# 3_Power.net
KiCad netlist of a schematic drawn in Altium Designer
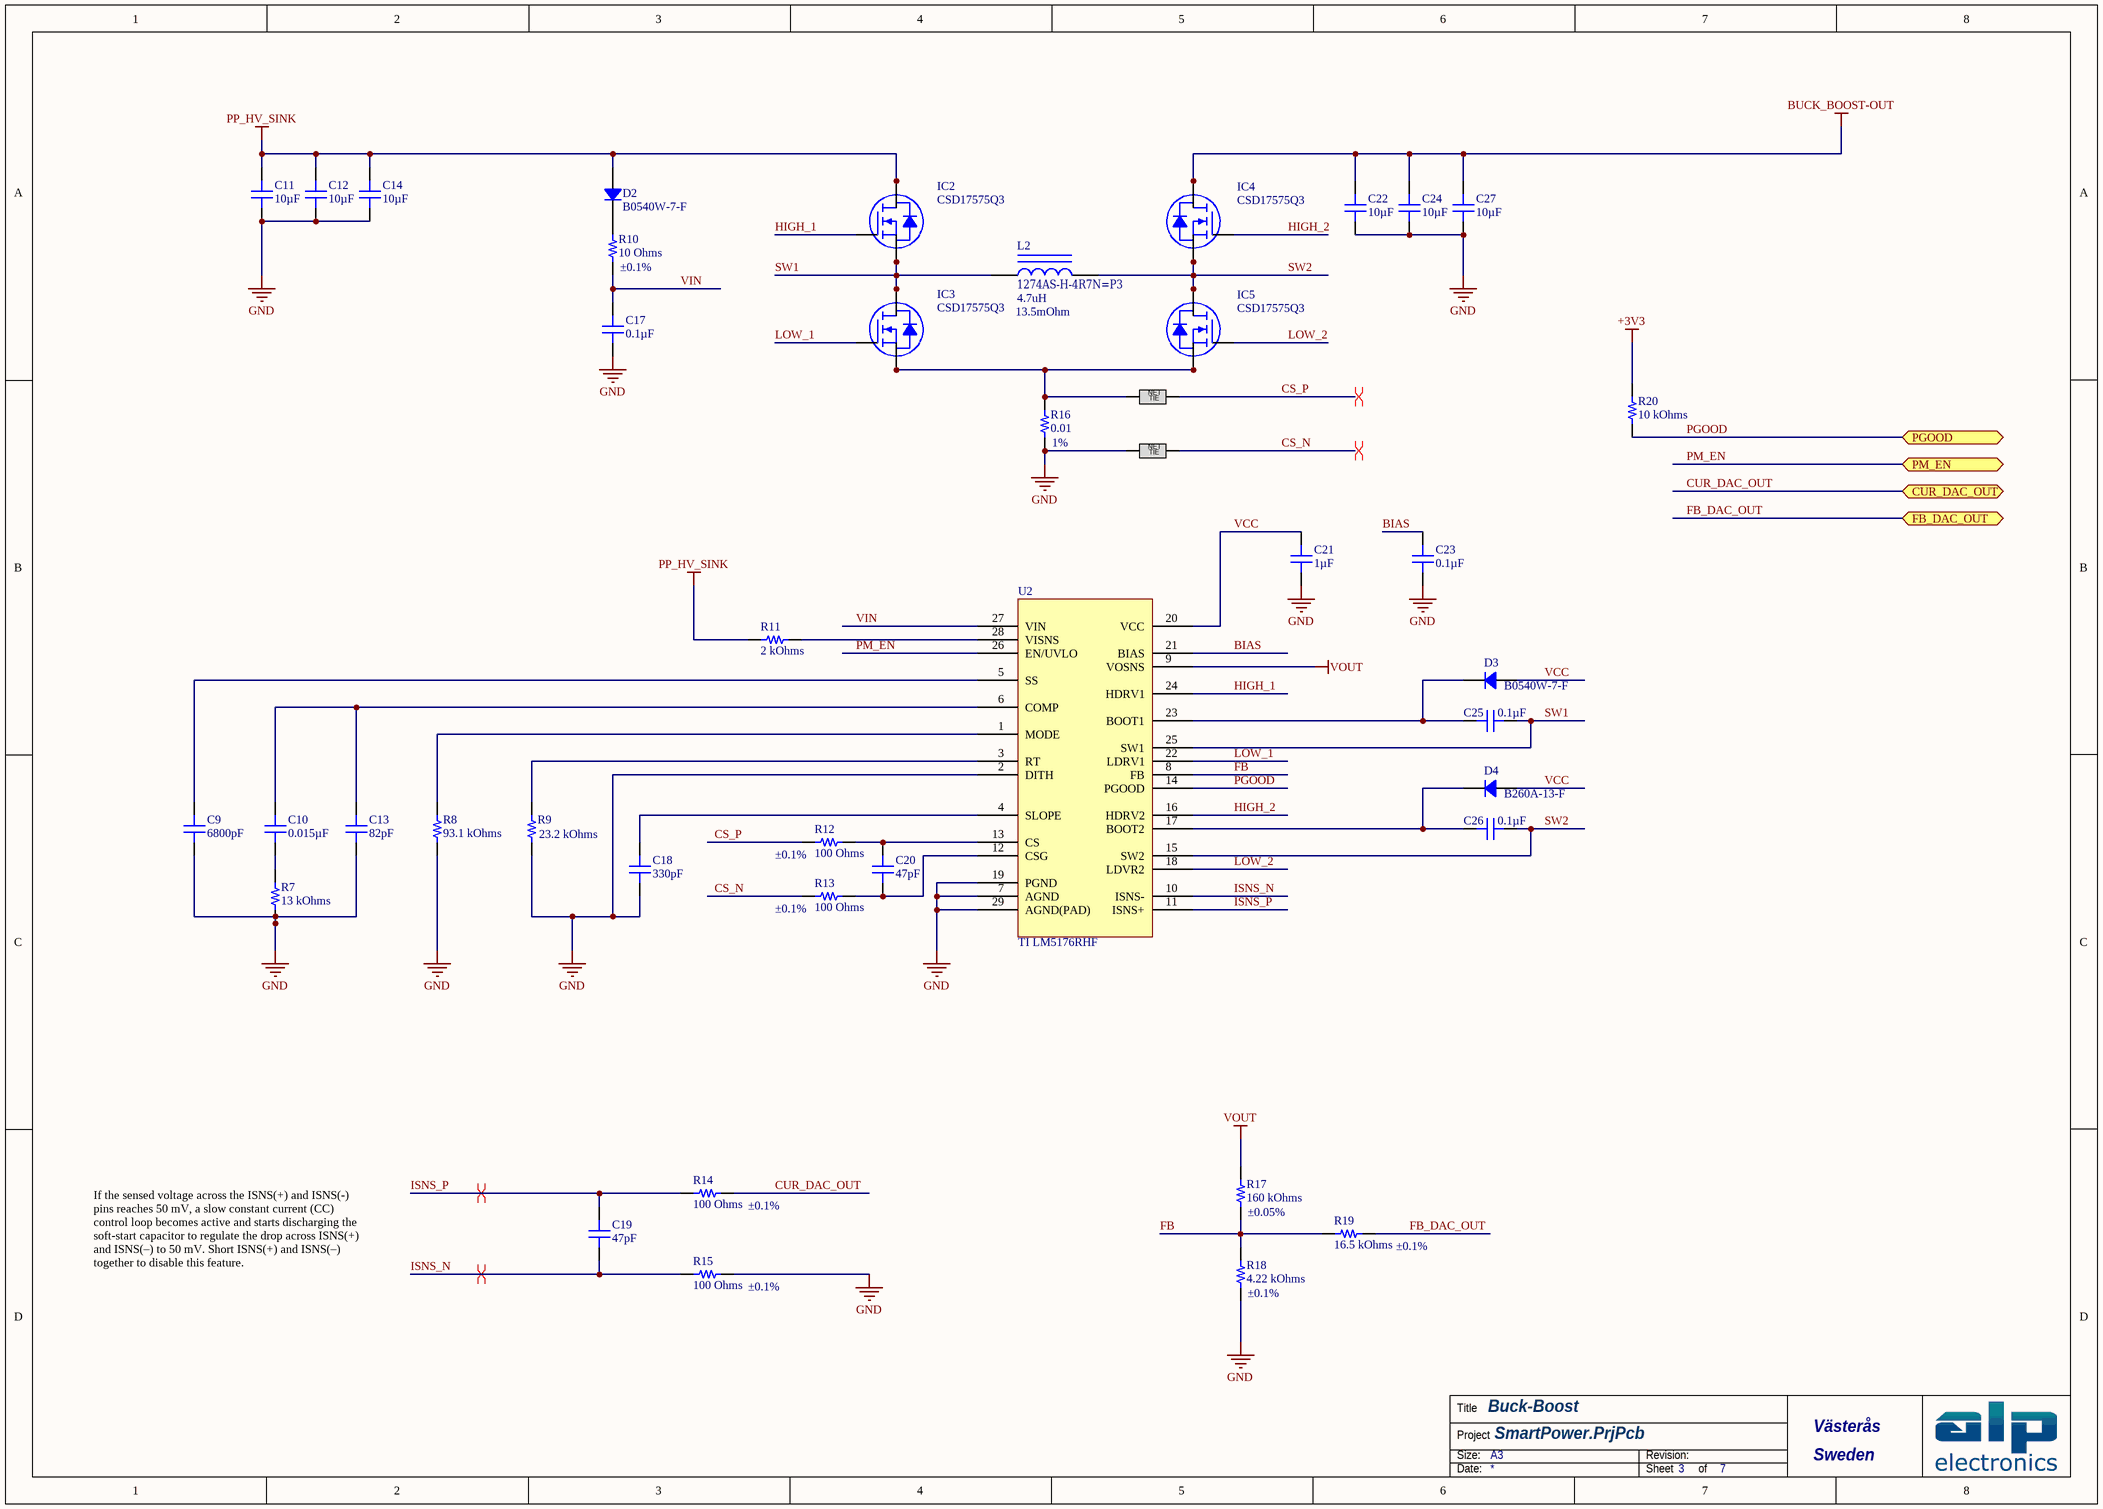
[diagram p0: [3] Power.SchDoc]

(export (version "E")
  (design (tool "Eeschema 10.0.6"))
  (components
    (comp (ref "C9")
      (value "6800pF")
      (footprint "CAP 0603_1608")
      (description "CAP CER 6800PF 50V X7R 0603")
      (fields
        (field (name "PART NUMBER") "0603B682K500CT")
        (field (name "MANUFACTURER") "Walsin Technology Corporation")
      )
      (libsource (lib "Celestial Altium Library - altium_library") (part "Capacitor"))
    )
    (comp (ref "C10")
      (value "0.015µF")
      (footprint "CAP 0603_1608")
      (description "CAP CER 0.015UF 50V X7R 0603")
      (fields
        (field (name "PART NUMBER") "0603B153K500CT")
        (field (name "MANUFACTURER") "Walsin Technology Corporation")
      )
      (libsource (lib "Celestial Altium Library - altium_library") (part "Capacitor"))
    )
    (comp (ref "C11")
      (value "10µF")
      (footprint "CAP 2220_5650 2.5MM")
      (description "CAP CER 10UF 50V X7R 2220")
      (fields
        (field (name "PART NUMBER") "C5750X7R1H106M230KB")
        (field (name "MANUFACTURER") "TDK Corporation")
      )
      (libsource (lib "Celestial Altium Library - altium_library") (part "Capacitor"))
    )
    (comp (ref "C12")
      (value "10µF")
      (footprint "CAP 2220_5650 2.5MM")
      (description "CAP CER 10UF 50V X7R 2220")
      (fields
        (field (name "PART NUMBER") "C5750X7R1H106M230KB")
        (field (name "MANUFACTURER") "TDK Corporation")
      )
      (libsource (lib "Celestial Altium Library - altium_library") (part "Capacitor"))
    )
    (comp (ref "C13")
      (value "82pF")
      (footprint "CAP 0603_1608")
      (description "CAP CER 82PF 100V C0G/NP0 0603")
      (fields (field (name "PART NUMBER") "06031A820GAT2A") (field (name "MANUFACTURER") "AVX Corporation"))
      (libsource (lib "Celestial Altium Library - altium_library") (part "Capacitor"))
    )
    (comp (ref "C14")
      (value "10µF")
      (footprint "CAP 2220_5650 2.5MM")
      (description "CAP CER 10UF 50V X7R 2220")
      (fields
        (field (name "PART NUMBER") "C5750X7R1H106M230KB")
        (field (name "MANUFACTURER") "TDK Corporation")
      )
      (libsource (lib "Celestial Altium Library - altium_library") (part "Capacitor"))
    )
    (comp (ref "C17")
      (value "0.1µF")
      (footprint "CAP 0603_1608")
      (description "CAP CER 0.1UF 50V X7R 0603")
      (fields (field (name "PART NUMBER") "0603BB104K500NGT") (field (name "MANUFACTURER") "Knowles Novacap"))
      (libsource (lib "Celestial Altium Library - altium_library") (part "Capacitor"))
    )
    (comp (ref "C18")
      (value "330pF")
      (footprint "CAP 0603_1608")
      (description "CAP CER 330PF 100V C0G/NP0 0603")
      (fields
        (field (name "PART NUMBER") "0603N331J101CT")
        (field (name "MANUFACTURER") "Walsin Technology Corporation")
      )
      (libsource (lib "Celestial Altium Library - altium_library") (part "Capacitor"))
    )
    (comp (ref "C19")
      (value "47pF")
      (footprint "CAP 0603_1608")
      (description "CAP CER 47PF 50V C0G/NP0 0603")
      (fields
        (field (name "PART NUMBER") "500X14N470MV4T")
        (field (name "MANUFACTURER") "Johanson Dielectrics Inc.")
      )
      (libsource (lib "Celestial Altium Library - altium_library") (part "Capacitor"))
    )
    (comp (ref "C20")
      (value "47pF")
      (footprint "CAP 0603_1608")
      (description "CAP CER 47PF 50V C0G/NP0 0603")
      (fields
        (field (name "PART NUMBER") "500X14N470MV4T")
        (field (name "MANUFACTURER") "Johanson Dielectrics Inc.")
      )
      (libsource (lib "Celestial Altium Library - altium_library") (part "Capacitor"))
    )
    (comp (ref "C21")
      (value "1µF")
      (footprint "CAP 0603_1608")
      (description "CAP CER 1UF 50V X7R 0603")
      (fields (field (name "PART NUMBER") "06035C105KAT2A") (field (name "MANUFACTURER") "AVX Corporation"))
      (libsource (lib "Celestial Altium Library - altium_library") (part "Capacitor"))
    )
    (comp (ref "C22")
      (value "10µF")
      (footprint "CAP 2220_5650 2.5MM")
      (description "CAP CER 10UF 50V X7R 2220")
      (fields
        (field (name "PART NUMBER") "C5750X7R1H106M230KB")
        (field (name "MANUFACTURER") "TDK Corporation")
      )
      (libsource (lib "Celestial Altium Library - altium_library") (part "Capacitor"))
    )
    (comp (ref "C23")
      (value "0.1µF")
      (footprint "CAP 0603_1608")
      (description "CAP CER 0.1UF 50V X7R 0603")
      (fields (field (name "PART NUMBER") "0603BB104K500NGT") (field (name "MANUFACTURER") "Knowles Novacap"))
      (libsource (lib "Celestial Altium Library - altium_library") (part "Capacitor"))
    )
    (comp (ref "C24")
      (value "10µF")
      (footprint "CAP 2220_5650 2.5MM")
      (description "CAP CER 10UF 50V X7R 2220")
      (fields
        (field (name "PART NUMBER") "C5750X7R1H106M230KB")
        (field (name "MANUFACTURER") "TDK Corporation")
      )
      (libsource (lib "Celestial Altium Library - altium_library") (part "Capacitor"))
    )
    (comp (ref "C25")
      (value "0.1µF")
      (footprint "CAP 0603_1608")
      (description "CAP CER 0.1UF 50V X7R 0603")
      (fields (field (name "PART NUMBER") "0603BB104K500NGT") (field (name "MANUFACTURER") "Knowles Novacap"))
      (libsource (lib "Celestial Altium Library - altium_library") (part "Capacitor"))
    )
    (comp (ref "C26")
      (value "0.1µF")
      (footprint "CAP 0603_1608")
      (description "CAP CER 0.1UF 50V X7R 0603")
      (fields (field (name "PART NUMBER") "0603BB104K500NGT") (field (name "MANUFACTURER") "Knowles Novacap"))
      (libsource (lib "Celestial Altium Library - altium_library") (part "Capacitor"))
    )
    (comp (ref "C27")
      (value "10µF")
      (footprint "CAP 2220_5650 2.5MM")
      (description "CAP CER 10UF 50V X7R 2220")
      (fields
        (field (name "PART NUMBER") "C5750X7R1H106M230KB")
        (field (name "MANUFACTURER") "TDK Corporation")
      )
      (libsource (lib "Celestial Altium Library - altium_library") (part "Capacitor"))
    )
    (comp (ref "D2")
      (value "B0540W-7-F")
      (footprint "SOD-123")
      (description "DIODE SCHOTTKY 40V 500MA SOD123")
      (fields (field (name "MANUFACTURER") "Diodes Incorporated"))
      (libsource (lib "Celestial Library Database") (part "Diode"))
    )
    (comp (ref "D3")
      (value "B0540W-7-F")
      (footprint "SOD-123")
      (description "DIODE SCHOTTKY 40V 500MA SOD123")
      (fields (field (name "MANUFACTURER") "Diodes Incorporated"))
      (libsource (lib "Celestial Library Database") (part "Diode"))
    )
    (comp (ref "D4")
      (value "B260A-13-F")
      (footprint "DO214AC SMA")
      (description "DIODE SCHOTTKY 60V 2A SMA")
      (fields (field (name "MANUFACTURER") "Diodes Incorporated"))
      (libsource (lib "Celestial Library Database") (part "Diode"))
    )
    (comp (ref "IC2")
      (value "CSD17575Q3")
      (footprint "TI SON-8 Q3")
      (description "MOSFET N-CH 30V 50A")
      (fields (field (name "PART NUMBER") "CSD17308Q3T") (field (name "MANUFACTURER") "Texas Instruments"))
      (libsource (lib "") (part "TI CSD MOSFET N-CH Q3_1"))
    )
    (comp (ref "IC3")
      (value "CSD17575Q3")
      (footprint "TI SON-8 Q3")
      (description "MOSFET N-CH 30V 50A")
      (fields (field (name "PART NUMBER") "CSD17308Q3T") (field (name "MANUFACTURER") "Texas Instruments"))
      (libsource (lib "") (part "TI CSD MOSFET N-CH Q3_1"))
    )
    (comp (ref "IC4")
      (value "CSD17575Q3")
      (footprint "TI SON-8 Q3")
      (description "MOSFET N-CH 30V 50A")
      (fields (field (name "PART NUMBER") "CSD17308Q3T") (field (name "MANUFACTURER") "Texas Instruments"))
      (libsource (lib "Celestial Library Database") (part "TI CSD MOSFET N-CH Q3"))
    )
    (comp (ref "IC5")
      (value "CSD17575Q3")
      (footprint "TI SON-8 Q3")
      (description "MOSFET N-CH 30V 50A")
      (fields (field (name "PART NUMBER") "CSD17308Q3T") (field (name "MANUFACTURER") "Texas Instruments"))
      (libsource (lib "Celestial Library Database") (part "TI CSD MOSFET N-CH Q3"))
    )
    (comp (ref "L2")
      (value "‎1274AS-H-4R7N=P3‎")
      (footprint "Component 3D Footprint:MURATA 1274AS")
      (description "Magnetic-Core Inductor")
      (fields
        (field (name "ALTIUM_VALUE") "4.7uH")
        (field (name "DCR") "13.5mOhm")
        (field (name "PUBLISHER") "Altium Limited")
      )
      (libsource (lib "Miscellaneous Devices") (part "Inductor Iron"))
    )
    (comp (ref "NetTie1")
      (value "Net Tie")
      (footprint "3D FootPrint_Backup:Net_Tie_2x0.156mm")
      (libsource (lib "Altium Component") (part "Net Tie"))
    )
    (comp (ref "NetTie2")
      (value "Net Tie")
      (footprint "3D FootPrint_Backup:Net_Tie_2x0.156mm")
      (libsource (lib "Altium Component") (part "Net Tie"))
    )
    (comp (ref "R7")
      (value "13 kOhms")
      (footprint "RES 0603_1608")
      (description "RES SMD 13K OHM 0.5% 1/5W 0603")
      (fields
        (field (name "PART NUMBER") "ERJ-PB3D1302V")
        (field (name "MANUFACTURER") "Panasonic Electronic Components")
      )
      (libsource (lib "Celestial Altium Library - altium_library") (part "Resistor"))
    )
    (comp (ref "R8")
      (value "93.1 kOhms")
      (footprint "RES 0603_1608")
      (description "RES SMD 93.1K OHM 0.5% 1/5W 0603")
      (fields
        (field (name "PART NUMBER") "ERJ-PB3D9312V")
        (field (name "MANUFACTURER") "Panasonic Electronic Components")
      )
      (libsource (lib "Celestial Altium Library - altium_library") (part "Resistor"))
    )
    (comp (ref "R9")
      (value "23.2 kOhms")
      (footprint "RES 0603_1608")
      (description "RES 23.2K OHM 0.5% 1/10W 0603")
      (fields
        (field (name "PART NUMBER") "RNCF0603DTE23K2")
        (field (name "MANUFACTURER") "Stackpole Electronics Inc")
      )
      (libsource (lib "Celestial Altium Library - altium_library") (part "Resistor"))
    )
    (comp (ref "R10")
      (value "10 Ohms")
      (footprint "RES 0603_1608")
      (description "RES SMD 10 OHM 0.1% 1/10W 0603")
      (fields
        (field (name "PART NUMBER") "RT0603BRD0710RL")
        (field (name "MANUFACTURER") "Yageo")
        (field (name "TOLERANCE") "±0.1%")
      )
      (libsource (lib "Celestial Altium Library - altium_library") (part "Resistor"))
    )
    (comp (ref "R11")
      (value "2 kOhms")
      (footprint "RES 0603_1608")
      (description "RES SMD 2K OHM 5% 1/10W 0603")
      (fields (field (name "PART NUMBER") "CR0603-JW-202ELF") (field (name "MANUFACTURER") "Bourns Inc."))
      (libsource (lib "Celestial Altium Library - altium_library") (part "Resistor"))
    )
    (comp (ref "R12")
      (value "100 Ohms")
      (footprint "RES 0603_1608")
      (description "RES 100 OHM 0.1% 1/16W 0603")
      (fields
        (field (name "PART NUMBER") "RNCS0603BKE100R")
        (field (name "MANUFACTURER") "Stackpole Electronics Inc")
        (field (name "TOLERANCE") "±0.1%")
      )
      (libsource (lib "Celestial Altium Library - altium_library") (part "Resistor"))
    )
    (comp (ref "R13")
      (value "100 Ohms")
      (footprint "RES 0603_1608")
      (description "RES 100 OHM 0.1% 1/16W 0603")
      (fields
        (field (name "PART NUMBER") "RNCS0603BKE100R")
        (field (name "MANUFACTURER") "Stackpole Electronics Inc")
        (field (name "TOLERANCE") "±0.1%")
      )
      (libsource (lib "Celestial Altium Library - altium_library") (part "Resistor"))
    )
    (comp (ref "R14")
      (value "100 Ohms")
      (footprint "RES 0603_1608")
      (description "RES 100 OHM 0.1% 1/16W 0603")
      (fields
        (field (name "PART NUMBER") "RNCS0603BKE100R")
        (field (name "MANUFACTURER") "Stackpole Electronics Inc")
        (field (name "TOLERANCE") "±0.1%")
      )
      (libsource (lib "Celestial Altium Library - altium_library") (part "Resistor"))
    )
    (comp (ref "R15")
      (value "100 Ohms")
      (footprint "RES 0603_1608")
      (description "RES 100 OHM 0.1% 1/16W 0603")
      (fields
        (field (name "PART NUMBER") "RNCS0603BKE100R")
        (field (name "MANUFACTURER") "Stackpole Electronics Inc")
        (field (name "TOLERANCE") "±0.1%")
      )
      (libsource (lib "Celestial Altium Library - altium_library") (part "Resistor"))
    )
    (comp (ref "R16")
      (value "0.01")
      (footprint "STACKPOLE CSR2512")
      (description "RES SMD 0.01 OHM 1% 2W 2512")
      (fields
        (field (name "PART NUMBER") "CSR2512FK10L0")
        (field (name "MANUFACTURER") "Stackpole Electronics Inc.")
        (field (name "TOLERANCE") "1%")
      )
      (libsource (lib "Celestial Library Database") (part "Resistor"))
    )
    (comp (ref "R17")
      (value "160 kOhms")
      (footprint "RES 0603_1608")
      (description "RES SMD 160KOHM 0.05% 1/10W 0603")
      (fields
        (field (name "PART NUMBER") "RG1608N-164-W-T1")
        (field (name "MANUFACTURER") "Susumu")
        (field (name "TOLERANCE") "±0.05%")
      )
      (libsource (lib "Celestial Altium Library - altium_library") (part "Resistor"))
    )
    (comp (ref "R18")
      (value "4.22 kOhms")
      (footprint "RES 0603_1608")
      (description "RES SMD 4.22K OHM 0.1% 1/5W 0603")
      (fields
        (field (name "PART NUMBER") "ERJ-PB3B4221V")
        (field (name "MANUFACTURER") "Panasonic Electronic Components")
        (field (name "TOLERANCE") "±0.1%")
      )
      (libsource (lib "Celestial Altium Library - altium_library") (part "Resistor"))
    )
    (comp (ref "R19")
      (value "16.5 kOhms")
      (footprint "RES 0603_1608")
      (description "RES SMD 16.5KOHM 0.1% 1/10W 0603")
      (fields
        (field (name "PART NUMBER") "ERA-3AEB1652V")
        (field (name "MANUFACTURER") "Panasonic Electronic Components")
        (field (name "TOLERANCE") "±0.1%")
      )
      (libsource (lib "Celestial Altium Library - altium_library") (part "Resistor"))
    )
    (comp (ref "R20")
      (value "10 kOhms")
      (footprint "RES 0603_1608")
      (description "RES SMD 10K OHM 5% 1/10W 0603")
      (fields (field (name "PART NUMBER") "CRCW060310K0JNEA") (field (name "MANUFACTURER") "Vishay Dale"))
      (libsource (lib "Celestial Altium Library - altium_library") (part "Resistor"))
    )
    (comp (ref "U2")
      (value "TI LM5176RHF")
      (footprint "Leadless:TI VQFN-28 RHF")
      (description "55-V Wide VIN synchronous 4-switch buck-boost controller")
      (libsource (lib "Altium Component") (part "TI LM5176RHF"))
    )
  )
  (nets
    (net (code "1") (name "+3V3") (class "Default")
      (node (ref "R20") (pin "1") (pinfunction "1_1") (pintype "passive"))
    )
    (net (code "2") (name "/BIAS") (class "Default")
      (node (ref "C23") (pin "2") (pinfunction "2_2") (pintype "passive"))
      (node (ref "U2") (pin "21") (pinfunction "BIAS_21") (pintype "passive"))
    )
    (net (code "3") (name "/CS_N") (class "Default")
      (node (ref "NetTie2") (pin "2") (pinfunction "2_2") (pintype "passive"))
      (node (ref "R13") (pin "1") (pinfunction "1_1") (pintype "passive"))
    )
    (net (code "4") (name "/CS_P") (class "Default")
      (node (ref "NetTie1") (pin "2") (pinfunction "2_2") (pintype "passive"))
      (node (ref "R12") (pin "1") (pinfunction "1_1") (pintype "passive"))
    )
    (net (code "5") (name "/CUR_DAC_OUT") (class "Default")
      (node (ref "R14") (pin "2") (pinfunction "2_2") (pintype "passive"))
    )
    (net (code "6") (name "/FB") (class "Default")
      (node (ref "R17") (pin "1") (pinfunction "1_1") (pintype "passive"))
      (node (ref "R18") (pin "2") (pinfunction "2_2") (pintype "passive"))
      (node (ref "R19") (pin "1") (pinfunction "1_1") (pintype "passive"))
      (node (ref "U2") (pin "8") (pinfunction "FB_8") (pintype "passive"))
    )
    (net (code "7") (name "/FB_DAC_OUT") (class "Default")
      (node (ref "R19") (pin "2") (pinfunction "2_2") (pintype "passive"))
    )
    (net (code "8") (name "/HIGH_1") (class "Default")
      (node (ref "IC2") (pin "4") (pinfunction "G_4") (pintype "passive"))
      (node (ref "U2") (pin "24") (pinfunction "HDRV1_24") (pintype "passive"))
    )
    (net (code "9") (name "/HIGH_2") (class "Default")
      (node (ref "IC4") (pin "4") (pinfunction "G_4") (pintype "passive"))
      (node (ref "U2") (pin "16") (pinfunction "HDRV2_16") (pintype "passive"))
    )
    (net (code "10") (name "/ISNS_N") (class "Default")
      (node (ref "C19") (pin "1") (pinfunction "1_1") (pintype "passive"))
      (node (ref "R15") (pin "1") (pinfunction "1_1") (pintype "passive"))
      (node (ref "U2") (pin "10") (pinfunction "ISNS-_10") (pintype "passive"))
    )
    (net (code "11") (name "/ISNS_P") (class "Default")
      (node (ref "C19") (pin "2") (pinfunction "2_2") (pintype "passive"))
      (node (ref "R14") (pin "1") (pinfunction "1_1") (pintype "passive"))
      (node (ref "U2") (pin "11") (pinfunction "ISNS+_11") (pintype "passive"))
    )
    (net (code "12") (name "/LOW_1") (class "Default")
      (node (ref "IC3") (pin "4") (pinfunction "G_4") (pintype "passive"))
      (node (ref "U2") (pin "22") (pinfunction "LDRV1_22") (pintype "passive"))
    )
    (net (code "13") (name "/LOW_2") (class "Default")
      (node (ref "IC5") (pin "4") (pinfunction "G_4") (pintype "passive"))
      (node (ref "U2") (pin "18") (pinfunction "LDVR2_18") (pintype "passive"))
    )
    (net (code "14") (name "/PGOOD") (class "Default")
      (node (ref "R20") (pin "2") (pinfunction "2_2") (pintype "passive"))
      (node (ref "U2") (pin "14") (pinfunction "PGOOD_14") (pintype "passive"))
    )
    (net (code "15") (name "/PM_EN") (class "Default")
      (node (ref "U2") (pin "26") (pinfunction "EN/UVLO_26") (pintype "passive"))
    )
    (net (code "16") (name "/SW1") (class "Default")
      (node (ref "C25") (pin "1") (pinfunction "1_1") (pintype "passive"))
      (node (ref "IC2") (pin "1") (pinfunction "S_1") (pintype "passive"))
      (node (ref "IC2") (pin "2") (pinfunction "S_2") (pintype "passive"))
      (node (ref "IC2") (pin "3") (pinfunction "S_3") (pintype "passive"))
      (node (ref "IC3") (pin "5") (pinfunction "D_5") (pintype "passive"))
      (node (ref "IC3") (pin "6") (pinfunction "D_6") (pintype "passive"))
      (node (ref "IC3") (pin "7") (pinfunction "D_7") (pintype "passive"))
      (node (ref "IC3") (pin "8") (pinfunction "D_8") (pintype "passive"))
      (node (ref "L2") (pin "1") (pinfunction "1_1") (pintype "passive"))
      (node (ref "U2") (pin "25") (pinfunction "SW1_25") (pintype "passive"))
    )
    (net (code "17") (name "/SW2") (class "Default")
      (node (ref "C26") (pin "1") (pinfunction "1_1") (pintype "passive"))
      (node (ref "IC4") (pin "1") (pinfunction "S_1") (pintype "passive"))
      (node (ref "IC4") (pin "2") (pinfunction "S_2") (pintype "passive"))
      (node (ref "IC4") (pin "3") (pinfunction "S_3") (pintype "passive"))
      (node (ref "IC5") (pin "5") (pinfunction "D_5") (pintype "passive"))
      (node (ref "IC5") (pin "6") (pinfunction "D_6") (pintype "passive"))
      (node (ref "IC5") (pin "7") (pinfunction "D_7") (pintype "passive"))
      (node (ref "IC5") (pin "8") (pinfunction "D_8") (pintype "passive"))
      (node (ref "L2") (pin "2") (pinfunction "2_2") (pintype "passive"))
      (node (ref "U2") (pin "15") (pinfunction "SW2_15") (pintype "passive"))
    )
    (net (code "18") (name "/VCC") (class "Default")
      (node (ref "C21") (pin "2") (pinfunction "2_2") (pintype "passive"))
      (node (ref "D3") (pin "1") (pinfunction "1_1") (pintype "passive"))
      (node (ref "D4") (pin "1") (pinfunction "1_1") (pintype "passive"))
      (node (ref "U2") (pin "20") (pinfunction "VCC_20") (pintype "passive"))
    )
    (net (code "19") (name "/VIN") (class "Default")
      (node (ref "C17") (pin "1") (pinfunction "1_1") (pintype "passive"))
      (node (ref "R10") (pin "1") (pinfunction "1_1") (pintype "passive"))
      (node (ref "U2") (pin "27") (pinfunction "VIN_27") (pintype "passive"))
    )
    (net (code "20") (name "BUCK_BOOST-OUT") (class "Default")
      (node (ref "C22") (pin "2") (pinfunction "2_2") (pintype "passive"))
      (node (ref "C24") (pin "2") (pinfunction "2_2") (pintype "passive"))
      (node (ref "C27") (pin "2") (pinfunction "2_2") (pintype "passive"))
      (node (ref "IC4") (pin "5") (pinfunction "D_5") (pintype "passive"))
      (node (ref "IC4") (pin "6") (pinfunction "D_6") (pintype "passive"))
      (node (ref "IC4") (pin "7") (pinfunction "D_7") (pintype "passive"))
      (node (ref "IC4") (pin "8") (pinfunction "D_8") (pintype "passive"))
    )
    (net (code "21") (name "GND") (class "Default")
      (node (ref "C11") (pin "1") (pinfunction "1_1") (pintype "passive"))
      (node (ref "C12") (pin "1") (pinfunction "1_1") (pintype "passive"))
      (node (ref "C13") (pin "1") (pinfunction "1_1") (pintype "passive"))
      (node (ref "C14") (pin "1") (pinfunction "1_1") (pintype "passive"))
      (node (ref "C17") (pin "2") (pinfunction "2_2") (pintype "passive"))
      (node (ref "C18") (pin "1") (pinfunction "1_1") (pintype "passive"))
      (node (ref "C21") (pin "1") (pinfunction "1_1") (pintype "passive"))
      (node (ref "C22") (pin "1") (pinfunction "1_1") (pintype "passive"))
      (node (ref "C23") (pin "1") (pinfunction "1_1") (pintype "passive"))
      (node (ref "C24") (pin "1") (pinfunction "1_1") (pintype "passive"))
      (node (ref "C27") (pin "1") (pinfunction "1_1") (pintype "passive"))
      (node (ref "C9") (pin "1") (pinfunction "1_1") (pintype "passive"))
      (node (ref "NetTie2") (pin "1") (pinfunction "1_1") (pintype "passive"))
      (node (ref "R15") (pin "2") (pinfunction "2_2") (pintype "passive"))
      (node (ref "R16") (pin "1") (pinfunction "1_1") (pintype "passive"))
      (node (ref "R18") (pin "1") (pinfunction "1_1") (pintype "passive"))
      (node (ref "R7") (pin "1") (pinfunction "1_1") (pintype "passive"))
      (node (ref "R8") (pin "1") (pinfunction "1_1") (pintype "passive"))
      (node (ref "R9") (pin "1") (pinfunction "1_1") (pintype "passive"))
      (node (ref "U2") (pin "19") (pinfunction "PGND_19") (pintype "passive"))
      (node (ref "U2") (pin "2") (pinfunction "DITH_2") (pintype "passive"))
      (node (ref "U2") (pin "29") (pinfunction "AGND(PAD)_29") (pintype "passive"))
      (node (ref "U2") (pin "7") (pinfunction "AGND_7") (pintype "passive"))
    )
    (net (code "22") (name "Net-(C10-Pad1)") (class "Default")
      (node (ref "C10") (pin "1") (pinfunction "1_1") (pintype "passive"))
      (node (ref "R7") (pin "2") (pinfunction "2_2") (pintype "passive"))
    )
    (net (code "23") (name "Net-(D2-Pad2)") (class "Default")
      (node (ref "D2") (pin "2") (pinfunction "2_2") (pintype "passive"))
      (node (ref "R10") (pin "2") (pinfunction "2_2") (pintype "passive"))
    )
    (net (code "24") (name "Net-(IC3-S-Pad1)") (class "Default")
      (node (ref "IC3") (pin "1") (pinfunction "S_1") (pintype "passive"))
      (node (ref "IC3") (pin "2") (pinfunction "S_2") (pintype "passive"))
      (node (ref "IC3") (pin "3") (pinfunction "S_3") (pintype "passive"))
      (node (ref "IC5") (pin "1") (pinfunction "S_1") (pintype "passive"))
      (node (ref "IC5") (pin "2") (pinfunction "S_2") (pintype "passive"))
      (node (ref "IC5") (pin "3") (pinfunction "S_3") (pintype "passive"))
      (node (ref "NetTie1") (pin "1") (pinfunction "1_1") (pintype "passive"))
      (node (ref "R16") (pin "2") (pinfunction "2_2") (pintype "passive"))
    )
    (net (code "25") (name "Net-(U2-BOOT1)") (class "Default")
      (node (ref "C25") (pin "2") (pinfunction "2_2") (pintype "passive"))
      (node (ref "D3") (pin "2") (pinfunction "2_2") (pintype "passive"))
      (node (ref "U2") (pin "23") (pinfunction "BOOT1_23") (pintype "passive"))
    )
    (net (code "26") (name "Net-(U2-BOOT2)") (class "Default")
      (node (ref "C26") (pin "2") (pinfunction "2_2") (pintype "passive"))
      (node (ref "D4") (pin "2") (pinfunction "2_2") (pintype "passive"))
      (node (ref "U2") (pin "17") (pinfunction "BOOT2_17") (pintype "passive"))
    )
    (net (code "27") (name "Net-(U2-COMP)") (class "Default")
      (node (ref "C10") (pin "2") (pinfunction "2_2") (pintype "passive"))
      (node (ref "C13") (pin "2") (pinfunction "2_2") (pintype "passive"))
      (node (ref "U2") (pin "6") (pinfunction "COMP_6") (pintype "passive"))
    )
    (net (code "28") (name "Net-(U2-CS)") (class "Default")
      (node (ref "C20") (pin "2") (pinfunction "2_2") (pintype "passive"))
      (node (ref "R12") (pin "2") (pinfunction "2_2") (pintype "passive"))
      (node (ref "U2") (pin "13") (pinfunction "CS_13") (pintype "passive"))
    )
    (net (code "29") (name "Net-(U2-CSG)") (class "Default")
      (node (ref "C20") (pin "1") (pinfunction "1_1") (pintype "passive"))
      (node (ref "R13") (pin "2") (pinfunction "2_2") (pintype "passive"))
      (node (ref "U2") (pin "12") (pinfunction "CSG_12") (pintype "passive"))
    )
    (net (code "30") (name "Net-(U2-MODE)") (class "Default")
      (node (ref "R8") (pin "2") (pinfunction "2_2") (pintype "passive"))
      (node (ref "U2") (pin "1") (pinfunction "MODE_1") (pintype "passive"))
    )
    (net (code "31") (name "Net-(U2-RT)") (class "Default")
      (node (ref "R9") (pin "2") (pinfunction "2_2") (pintype "passive"))
      (node (ref "U2") (pin "3") (pinfunction "RT_3") (pintype "passive"))
    )
    (net (code "32") (name "Net-(U2-SLOPE)") (class "Default")
      (node (ref "C18") (pin "2") (pinfunction "2_2") (pintype "passive"))
      (node (ref "U2") (pin "4") (pinfunction "SLOPE_4") (pintype "passive"))
    )
    (net (code "33") (name "Net-(U2-SS)") (class "Default")
      (node (ref "C9") (pin "2") (pinfunction "2_2") (pintype "passive"))
      (node (ref "U2") (pin "5") (pinfunction "SS_5") (pintype "passive"))
    )
    (net (code "34") (name "Net-(U2-VISNS)") (class "Default")
      (node (ref "R11") (pin "2") (pinfunction "2_2") (pintype "passive"))
      (node (ref "U2") (pin "28") (pinfunction "VISNS_28") (pintype "passive"))
    )
    (net (code "35") (name "PP_HV_SINK") (class "Default")
      (node (ref "C11") (pin "2") (pinfunction "2_2") (pintype "passive"))
      (node (ref "C12") (pin "2") (pinfunction "2_2") (pintype "passive"))
      (node (ref "C14") (pin "2") (pinfunction "2_2") (pintype "passive"))
      (node (ref "D2") (pin "1") (pinfunction "1_1") (pintype "passive"))
      (node (ref "IC2") (pin "5") (pinfunction "D_5") (pintype "passive"))
      (node (ref "IC2") (pin "6") (pinfunction "D_6") (pintype "passive"))
      (node (ref "IC2") (pin "7") (pinfunction "D_7") (pintype "passive"))
      (node (ref "IC2") (pin "8") (pinfunction "D_8") (pintype "passive"))
      (node (ref "R11") (pin "1") (pinfunction "1_1") (pintype "passive"))
    )
    (net (code "36") (name "VOUT") (class "Default")
      (node (ref "R17") (pin "2") (pinfunction "2_2") (pintype "passive"))
      (node (ref "U2") (pin "9") (pinfunction "VOSNS_9") (pintype "passive"))
    )
  )
)
